# circuit.net
KiCad netlist of a schematic drawn in EAGLE
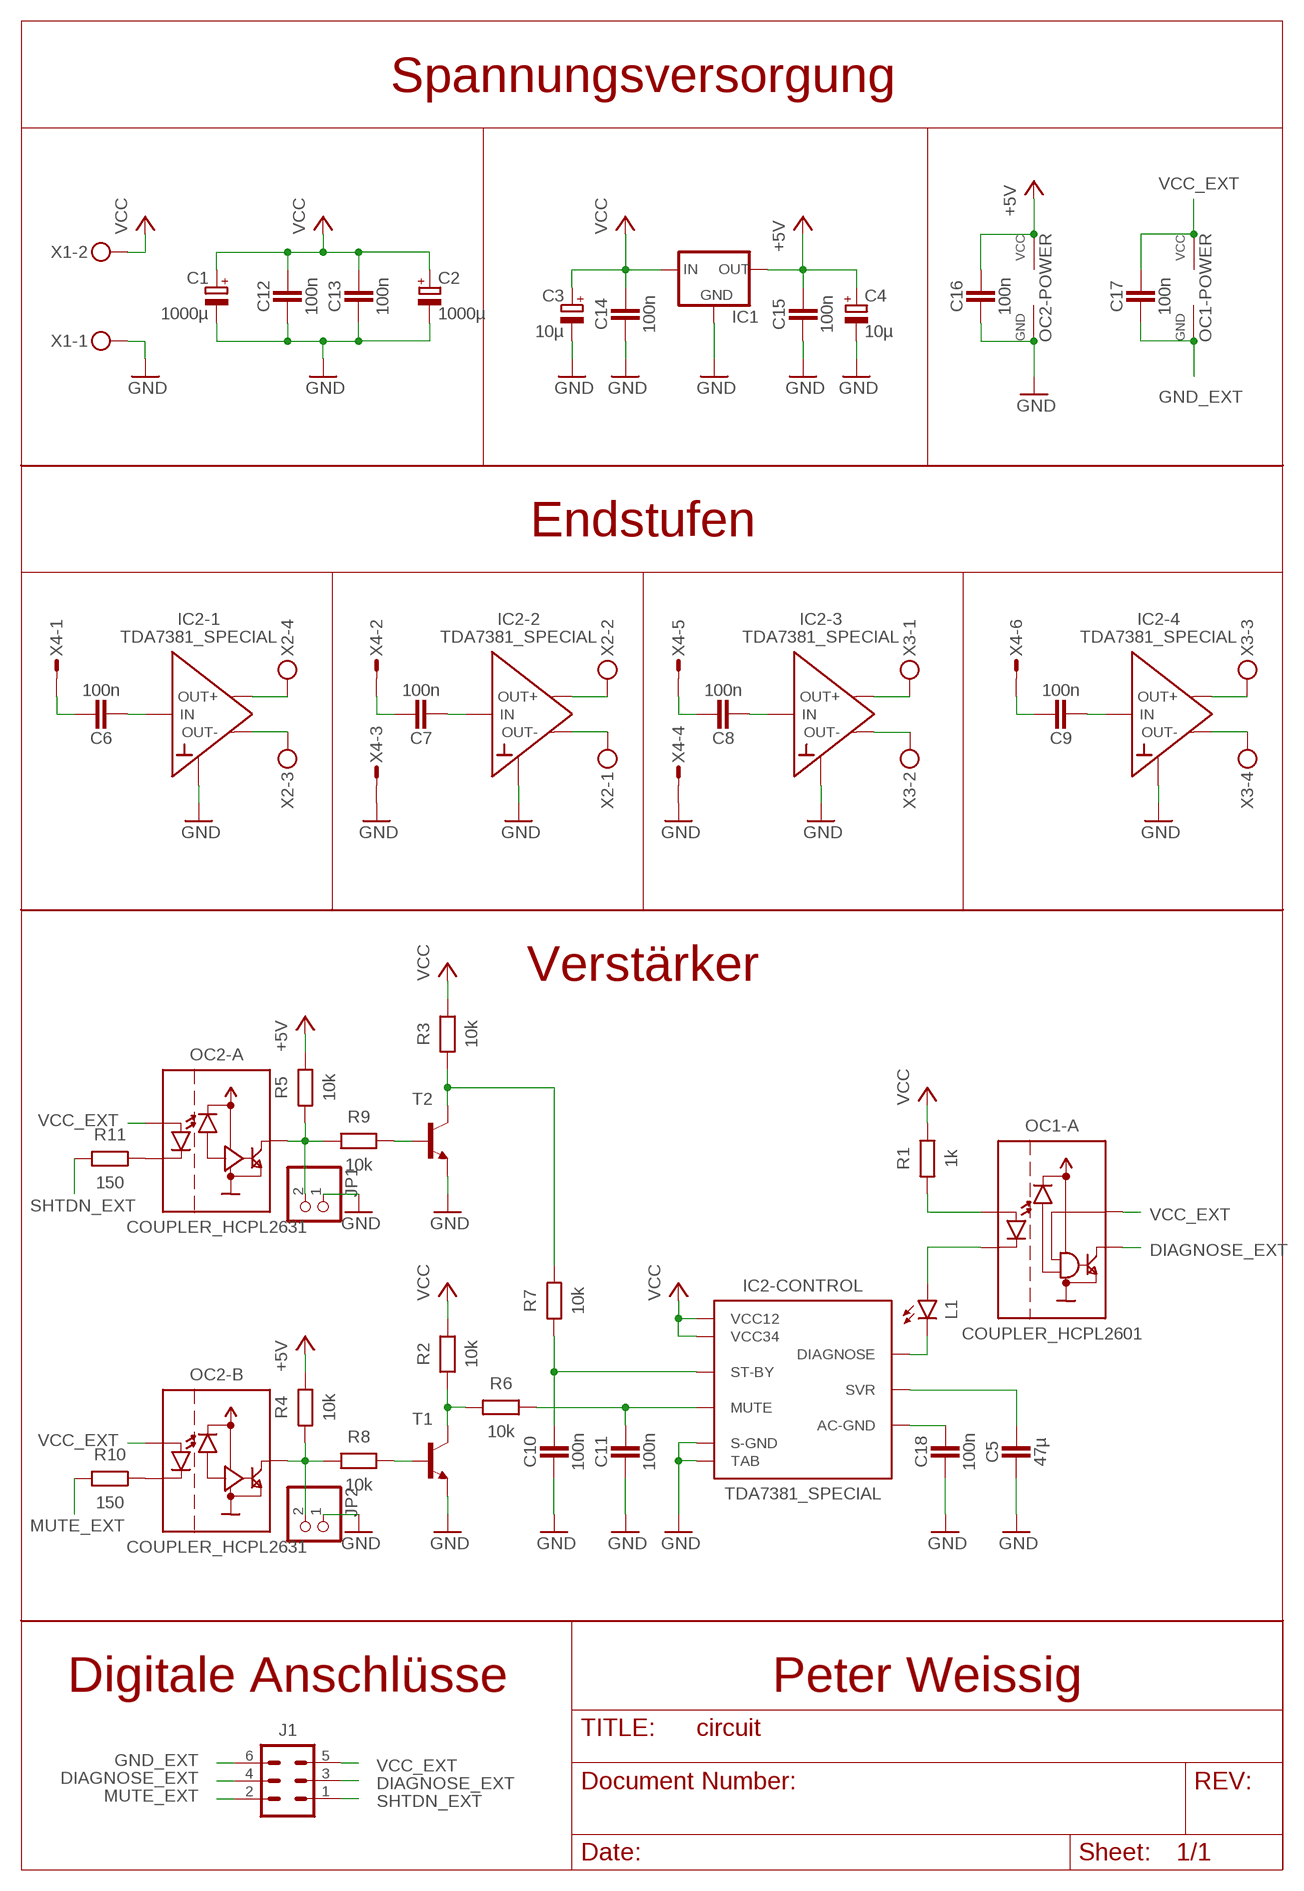
[diagram p0: schematic, sheet 1]

(export (version "E")
  (design (tool "Eeschema 10.0.6"))
  (components
    (comp (ref "C1")
      (value "1000µ")
      (footprint "eagle-import:E5-10,5")
      (libsource (lib "eagle-import") (part "CPOL-EUE5-10.5"))
    )
    (comp (ref "C2")
      (value "1000µ")
      (footprint "eagle-import:E5-10,5")
      (libsource (lib "eagle-import") (part "CPOL-EUE5-10.5"))
    )
    (comp (ref "C3")
      (value "10µ")
      (footprint "eagle-import:E2-5")
      (libsource (lib "eagle-import") (part "CPOL-EUE2-5"))
    )
    (comp (ref "C4")
      (value "10µ")
      (footprint "eagle-import:E2-5")
      (libsource (lib "eagle-import") (part "CPOL-EUE2-5"))
    )
    (comp (ref "C5")
      (value "47µ")
      (footprint "eagle-import:SMD_2312S")
      (libsource (lib "eagle-import") (part "CAPACITATOR-2312S"))
    )
    (comp (ref "C6")
      (value "100n")
      (footprint "eagle-import:C_THT_3")
      (libsource (lib "eagle-import") (part "CAPACITATOR-5MM"))
    )
    (comp (ref "C7")
      (value "100n")
      (footprint "eagle-import:C_THT_3")
      (libsource (lib "eagle-import") (part "CAPACITATOR-5MM"))
    )
    (comp (ref "C8")
      (value "100n")
      (footprint "eagle-import:C_THT_3")
      (libsource (lib "eagle-import") (part "CAPACITATOR-5MM"))
    )
    (comp (ref "C9")
      (value "100n")
      (footprint "eagle-import:C_THT_3")
      (libsource (lib "eagle-import") (part "CAPACITATOR-5MM"))
    )
    (comp (ref "C10")
      (value "100n")
      (footprint "eagle-import:C_THT_3")
      (libsource (lib "eagle-import") (part "CAPACITATOR-5MM"))
    )
    (comp (ref "C11")
      (value "100n")
      (footprint "eagle-import:C_THT_3")
      (libsource (lib "eagle-import") (part "CAPACITATOR-5MM"))
    )
    (comp (ref "C12")
      (value "100n")
      (footprint "eagle-import:SMD_1206")
      (libsource (lib "eagle-import") (part "CAPACITATOR-1206"))
    )
    (comp (ref "C13")
      (value "100n")
      (footprint "eagle-import:SMD_1206")
      (libsource (lib "eagle-import") (part "CAPACITATOR-1206"))
    )
    (comp (ref "C14")
      (value "100n")
      (footprint "eagle-import:SMD_1206")
      (libsource (lib "eagle-import") (part "CAPACITATOR-1206"))
    )
    (comp (ref "C15")
      (value "100n")
      (footprint "eagle-import:SMD_1206")
      (libsource (lib "eagle-import") (part "CAPACITATOR-1206"))
    )
    (comp (ref "C16")
      (value "100n")
      (footprint "eagle-import:SMD_1206")
      (libsource (lib "eagle-import") (part "CAPACITATOR-1206"))
    )
    (comp (ref "C17")
      (value "100n")
      (footprint "eagle-import:SMD_1206")
      (libsource (lib "eagle-import") (part "CAPACITATOR-1206"))
    )
    (comp (ref "C18")
      (value "100n")
      (footprint "eagle-import:SMD_1206")
      (libsource (lib "eagle-import") (part "CAPACITATOR-1206"))
    )
    (comp (ref "IC1")
      (value "78XXS")
      (footprint "eagle-import:78XXS")
      (libsource (lib "eagle-import") (part "78XXS"))
    )
    (comp (ref "IC2")
      (value "TDA7381_SPECIAL")
      (footprint "eagle-import:IC_FLEXIWATT25_SPECIAL")
      (libsource (lib "eagle-import") (part "TDA7381_SPECIAL"))
    )
    (comp (ref "J1")
      (value "STECKER_WANNE_6")
      (footprint "eagle-import:STECKER_WANNE_6")
      (libsource (lib "eagle-import") (part "STECKER_WANNE_6"))
    )
    (comp (ref "JP1")
      (value "PINHD-1X2")
      (footprint "eagle-import:1X02")
      (libsource (lib "eagle-import") (part "PINHD-1X2"))
    )
    (comp (ref "JP2")
      (value "PINHD-1X2")
      (footprint "eagle-import:1X02")
      (libsource (lib "eagle-import") (part "PINHD-1X2"))
    )
    (comp (ref "L1")
      (value "LED-3MM")
      (footprint "eagle-import:LED_3MM")
      (libsource (lib "eagle-import") (part "LED-3MM"))
    )
    (comp (ref "OC1")
      (value "COUPLER_HCPL2601")
      (footprint "eagle-import:IC_DIL08")
      (libsource (lib "eagle-import") (part "COUPLER_HCPL2601"))
    )
    (comp (ref "OC2")
      (value "COUPLER_HCPL2631")
      (footprint "eagle-import:IC_DIL08")
      (libsource (lib "eagle-import") (part "COUPLER_HCPL2631"))
    )
    (comp (ref "R1")
      (value "1k")
      (footprint "eagle-import:R_THT_4")
      (libsource (lib "eagle-import") (part "RESISTOR-10MM"))
    )
    (comp (ref "R2")
      (value "10k")
      (footprint "eagle-import:R_THT_4")
      (libsource (lib "eagle-import") (part "RESISTOR-10MM"))
    )
    (comp (ref "R3")
      (value "10k")
      (footprint "eagle-import:R_THT_4")
      (libsource (lib "eagle-import") (part "RESISTOR-10MM"))
    )
    (comp (ref "R4")
      (value "10k")
      (footprint "eagle-import:R_THT_4")
      (libsource (lib "eagle-import") (part "RESISTOR-10MM"))
    )
    (comp (ref "R5")
      (value "10k")
      (footprint "eagle-import:R_THT_4")
      (libsource (lib "eagle-import") (part "RESISTOR-10MM"))
    )
    (comp (ref "R6")
      (value "10k")
      (footprint "eagle-import:R_THT_4")
      (libsource (lib "eagle-import") (part "RESISTOR-10MM"))
    )
    (comp (ref "R7")
      (value "10k")
      (footprint "eagle-import:R_THT_4")
      (libsource (lib "eagle-import") (part "RESISTOR-10MM"))
    )
    (comp (ref "R8")
      (value "10k")
      (footprint "eagle-import:SMD_1206")
      (libsource (lib "eagle-import") (part "RESISTOR-1206"))
    )
    (comp (ref "R9")
      (value "10k")
      (footprint "eagle-import:SMD_1206")
      (libsource (lib "eagle-import") (part "RESISTOR-1206"))
    )
    (comp (ref "R10")
      (value "150")
      (footprint "eagle-import:SMD_1206")
      (libsource (lib "eagle-import") (part "RESISTOR-1206"))
    )
    (comp (ref "R11")
      (value "150")
      (footprint "eagle-import:SMD_1206")
      (libsource (lib "eagle-import") (part "RESISTOR-1206"))
    )
    (comp (ref "T1")
      (value "BC548-NPN-TO92-CBE")
      (footprint "eagle-import:TO92-CBE")
      (libsource (lib "eagle-import") (part "-NPN-TO92-CBEBC548"))
    )
    (comp (ref "T2")
      (value "BC548-NPN-TO92-CBE")
      (footprint "eagle-import:TO92-CBE")
      (libsource (lib "eagle-import") (part "-NPN-TO92-CBEBC548"))
    )
    (comp (ref "X1")
      (value "STECKER_SPG_2")
      (footprint "eagle-import:STECKER_SPG_2")
      (libsource (lib "eagle-import") (part "STECKER_SPG_2"))
    )
    (comp (ref "X2")
      (value "STECKER_SPG_4")
      (footprint "eagle-import:STECKER_SPG_4")
      (libsource (lib "eagle-import") (part "STECKER_SPG_4"))
    )
    (comp (ref "X3")
      (value "STECKER_SPG_4")
      (footprint "eagle-import:STECKER_SPG_4")
      (libsource (lib "eagle-import") (part "STECKER_SPG_4"))
    )
    (comp (ref "X4")
      (value "STECKER_MICROMATCH_6")
      (footprint "eagle-import:STECKER_MICROMATCH_6")
      (libsource (lib "eagle-import") (part "STECKER_MICROMATCH_6"))
    )
  )
  (nets
    (net (code "1") (name "+5V") (class "Default")
      (node (ref "C15") (pin "1") (pinfunction "1_1") (pintype "passive"))
      (node (ref "C16") (pin "1") (pinfunction "1_1") (pintype "passive"))
      (node (ref "C4") (pin "+") (pinfunction "+_+") (pintype "passive"))
      (node (ref "IC1") (pin "OUT") (pinfunction "OUT_OUT") (pintype "passive"))
      (node (ref "OC2") (pin "8") (pinfunction "VCC_8") (pintype "power_in"))
      (node (ref "R4") (pin "2") (pinfunction "P2_2") (pintype "passive"))
      (node (ref "R5") (pin "2") (pinfunction "P2_2") (pintype "passive"))
    )
    (net (code "2") (name "/DIAGNOSE_EXT") (class "Default")
      (node (ref "J1") (pin "3") (pinfunction "3_3") (pintype "passive"))
      (node (ref "J1") (pin "4") (pinfunction "4_4") (pintype "passive"))
      (node (ref "OC1") (pin "6") (pinfunction "O_6") (pintype "open_collector"))
    )
    (net (code "3") (name "/GND_EXT") (class "Default")
      (node (ref "C17") (pin "2") (pinfunction "2_2") (pintype "passive"))
      (node (ref "J1") (pin "6") (pinfunction "6_6") (pintype "passive"))
      (node (ref "OC1") (pin "5") (pinfunction "GND_5") (pintype "power_in"))
    )
    (net (code "4") (name "/MUTE_EXT") (class "Default")
      (node (ref "J1") (pin "2") (pinfunction "2_2") (pintype "passive"))
      (node (ref "R10") (pin "2") (pinfunction "P2_2") (pintype "passive"))
    )
    (net (code "5") (name "/SHTDN_EXT") (class "Default")
      (node (ref "J1") (pin "1") (pinfunction "1_1") (pintype "passive"))
      (node (ref "R11") (pin "2") (pinfunction "P2_2") (pintype "passive"))
    )
    (net (code "6") (name "/VCC_EXT") (class "Default")
      (node (ref "C17") (pin "1") (pinfunction "1_1") (pintype "passive"))
      (node (ref "J1") (pin "5") (pinfunction "5_5") (pintype "passive"))
      (node (ref "OC1") (pin "7") (pinfunction "I_EN_7") (pintype "input"))
      (node (ref "OC1") (pin "8") (pinfunction "VCC_8") (pintype "power_in"))
      (node (ref "OC2") (pin "1") (pinfunction "I_A_1") (pintype "input"))
      (node (ref "OC2") (pin "4") (pinfunction "I_A_4") (pintype "input"))
    )
    (net (code "7") (name "GND") (class "Default")
      (node (ref "C1") (pin "-") (pinfunction "-_-") (pintype "passive"))
      (node (ref "C10") (pin "1") (pinfunction "1_1") (pintype "passive"))
      (node (ref "C11") (pin "1") (pinfunction "1_1") (pintype "passive"))
      (node (ref "C12") (pin "2") (pinfunction "2_2") (pintype "passive"))
      (node (ref "C13") (pin "2") (pinfunction "2_2") (pintype "passive"))
      (node (ref "C14") (pin "2") (pinfunction "2_2") (pintype "passive"))
      (node (ref "C15") (pin "2") (pinfunction "2_2") (pintype "passive"))
      (node (ref "C16") (pin "2") (pinfunction "2_2") (pintype "passive"))
      (node (ref "C18") (pin "2") (pinfunction "2_2") (pintype "passive"))
      (node (ref "C2") (pin "-") (pinfunction "-_-") (pintype "passive"))
      (node (ref "C3") (pin "-") (pinfunction "-_-") (pintype "passive"))
      (node (ref "C4") (pin "-") (pinfunction "-_-") (pintype "passive"))
      (node (ref "C5") (pin "2") (pinfunction "2_2") (pintype "passive"))
      (node (ref "IC1") (pin "GND") (pinfunction "GND_GND") (pintype "input"))
      (node (ref "IC2") (pin "1") (pinfunction "TAB_1") (pintype "input"))
      (node (ref "IC2") (pin "13") (pinfunction "S-GND_13") (pintype "input"))
      (node (ref "IC2") (pin "18") (pinfunction "GND_18") (pintype "power_in"))
      (node (ref "IC2") (pin "2") (pinfunction "GND_2") (pintype "power_in"))
      (node (ref "IC2") (pin "24") (pinfunction "GND_24") (pintype "power_in"))
      (node (ref "IC2") (pin "8") (pinfunction "GND_8") (pintype "power_in"))
      (node (ref "JP1") (pin "1") (pinfunction "1_1") (pintype "passive"))
      (node (ref "JP2") (pin "1") (pinfunction "1_1") (pintype "passive"))
      (node (ref "OC2") (pin "5") (pinfunction "GND_5") (pintype "power_in"))
      (node (ref "T1") (pin "E") (pinfunction "E_E") (pintype "passive"))
      (node (ref "T2") (pin "E") (pinfunction "E_E") (pintype "passive"))
      (node (ref "X1") (pin "1") (pinfunction "KL_1") (pintype "passive"))
      (node (ref "X4") (pin "3") (pinfunction "S_3") (pintype "passive"))
      (node (ref "X4") (pin "4") (pinfunction "S_4") (pintype "passive"))
    )
    (net (code "8") (name "Net-(IC2A-IN)") (class "Default")
      (node (ref "C6") (pin "2") (pinfunction "2_2") (pintype "passive"))
      (node (ref "IC2") (pin "11") (pinfunction "IN_11") (pintype "input"))
    )
    (net (code "9") (name "Net-(IC2A-OUT+)") (class "Default")
      (node (ref "IC2") (pin "9") (pinfunction "OUT+_9") (pintype "output"))
      (node (ref "X2") (pin "4") (pinfunction "KL_4") (pintype "passive"))
    )
    (net (code "10") (name "Net-(IC2A-OUT-)") (class "Default")
      (node (ref "IC2") (pin "7") (pinfunction "OUT-_7") (pintype "output"))
      (node (ref "X2") (pin "3") (pinfunction "KL_3") (pintype "passive"))
    )
    (net (code "11") (name "Net-(IC2B-IN)") (class "Default")
      (node (ref "C7") (pin "2") (pinfunction "2_2") (pintype "passive"))
      (node (ref "IC2") (pin "12") (pinfunction "IN_12") (pintype "input"))
    )
    (net (code "12") (name "Net-(IC2B-OUT+)") (class "Default")
      (node (ref "IC2") (pin "5") (pinfunction "OUT+_5") (pintype "output"))
      (node (ref "X2") (pin "2") (pinfunction "KL_2") (pintype "passive"))
    )
    (net (code "13") (name "Net-(IC2B-OUT-)") (class "Default")
      (node (ref "IC2") (pin "3") (pinfunction "OUT-_3") (pintype "output"))
      (node (ref "X2") (pin "1") (pinfunction "KL_1") (pintype "passive"))
    )
    (net (code "14") (name "Net-(IC2C-IN)") (class "Default")
      (node (ref "C8") (pin "2") (pinfunction "2_2") (pintype "passive"))
      (node (ref "IC2") (pin "15") (pinfunction "IN_15") (pintype "input"))
    )
    (net (code "15") (name "Net-(IC2C-OUT+)") (class "Default")
      (node (ref "IC2") (pin "17") (pinfunction "OUT+_17") (pintype "output"))
      (node (ref "X3") (pin "1") (pinfunction "KL_1") (pintype "passive"))
    )
    (net (code "16") (name "Net-(IC2C-OUT-)") (class "Default")
      (node (ref "IC2") (pin "19") (pinfunction "OUT-_19") (pintype "output"))
      (node (ref "X3") (pin "2") (pinfunction "KL_2") (pintype "passive"))
    )
    (net (code "17") (name "Net-(IC2D-IN)") (class "Default")
      (node (ref "C9") (pin "2") (pinfunction "2_2") (pintype "passive"))
      (node (ref "IC2") (pin "14") (pinfunction "IN_14") (pintype "input"))
    )
    (net (code "18") (name "Net-(IC2D-OUT+)") (class "Default")
      (node (ref "IC2") (pin "21") (pinfunction "OUT+_21") (pintype "output"))
      (node (ref "X3") (pin "3") (pinfunction "KL_3") (pintype "passive"))
    )
    (net (code "19") (name "Net-(IC2D-OUT-)") (class "Default")
      (node (ref "IC2") (pin "23") (pinfunction "OUT-_23") (pintype "output"))
      (node (ref "X3") (pin "4") (pinfunction "KL_4") (pintype "passive"))
    )
    (net (code "20") (name "Net-(IC2E-AC-GND)") (class "Default")
      (node (ref "C18") (pin "1") (pinfunction "1_1") (pintype "passive"))
      (node (ref "IC2") (pin "16") (pinfunction "AC-GND_16") (pintype "power_in"))
    )
    (net (code "21") (name "Net-(IC2E-DIAGNOSE)") (class "Default")
      (node (ref "IC2") (pin "25") (pinfunction "DIAGNOSE_25") (pintype "open_collector"))
      (node (ref "L1") (pin "K") (pinfunction "C_K") (pintype "passive"))
    )
    (net (code "22") (name "Net-(IC2E-MUTE)") (class "Default")
      (node (ref "C11") (pin "2") (pinfunction "2_2") (pintype "passive"))
      (node (ref "IC2") (pin "22") (pinfunction "MUTE_22") (pintype "input"))
      (node (ref "R6") (pin "1") (pinfunction "P1_1") (pintype "passive"))
    )
    (net (code "23") (name "Net-(IC2E-ST-BY)") (class "Default")
      (node (ref "C10") (pin "2") (pinfunction "2_2") (pintype "passive"))
      (node (ref "IC2") (pin "4") (pinfunction "ST-BY_4") (pintype "input"))
      (node (ref "R7") (pin "1") (pinfunction "P1_1") (pintype "passive"))
    )
    (net (code "24") (name "Net-(IC2E-SVR)") (class "Default")
      (node (ref "C5") (pin "1") (pinfunction "1_1") (pintype "passive"))
      (node (ref "IC2") (pin "10") (pinfunction "SVR_10") (pintype "power_in"))
    )
    (net (code "25") (name "Net-(OC1A-I_A)") (class "Default")
      (node (ref "OC1") (pin "2") (pinfunction "I_A_2") (pintype "input"))
      (node (ref "R1") (pin "1") (pinfunction "P1_1") (pintype "passive"))
    )
    (net (code "26") (name "Net-(OC1A-I_K)") (class "Default")
      (node (ref "L1") (pin "A") (pinfunction "A_A") (pintype "passive"))
      (node (ref "OC1") (pin "3") (pinfunction "I_K_3") (pintype "input"))
    )
    (net (code "27") (name "Net-(OC2A-I_K)") (class "Default")
      (node (ref "OC2") (pin "2") (pinfunction "I_K_2") (pintype "input"))
      (node (ref "R11") (pin "1") (pinfunction "P1_1") (pintype "passive"))
    )
    (net (code "28") (name "Net-(OC2A-O)") (class "Default")
      (node (ref "JP1") (pin "2") (pinfunction "2_2") (pintype "passive"))
      (node (ref "OC2") (pin "7") (pinfunction "O_7") (pintype "open_collector"))
      (node (ref "R5") (pin "1") (pinfunction "P1_1") (pintype "passive"))
      (node (ref "R9") (pin "1") (pinfunction "P1_1") (pintype "passive"))
    )
    (net (code "29") (name "Net-(OC2B-I_K)") (class "Default")
      (node (ref "OC2") (pin "3") (pinfunction "I_K_3") (pintype "input"))
      (node (ref "R10") (pin "1") (pinfunction "P1_1") (pintype "passive"))
    )
    (net (code "30") (name "Net-(OC2B-O)") (class "Default")
      (node (ref "JP2") (pin "2") (pinfunction "2_2") (pintype "passive"))
      (node (ref "OC2") (pin "6") (pinfunction "O_6") (pintype "open_collector"))
      (node (ref "R4") (pin "1") (pinfunction "P1_1") (pintype "passive"))
      (node (ref "R8") (pin "1") (pinfunction "P1_1") (pintype "passive"))
    )
    (net (code "31") (name "Net-(R2-P2)") (class "Default")
      (node (ref "R2") (pin "2") (pinfunction "P2_2") (pintype "passive"))
      (node (ref "R6") (pin "2") (pinfunction "P2_2") (pintype "passive"))
      (node (ref "T1") (pin "C") (pinfunction "C_C") (pintype "passive"))
    )
    (net (code "32") (name "Net-(R3-P2)") (class "Default")
      (node (ref "R3") (pin "2") (pinfunction "P2_2") (pintype "passive"))
      (node (ref "R7") (pin "2") (pinfunction "P2_2") (pintype "passive"))
      (node (ref "T2") (pin "C") (pinfunction "C_C") (pintype "passive"))
    )
    (net (code "33") (name "Net-(R8-P2)") (class "Default")
      (node (ref "R8") (pin "2") (pinfunction "P2_2") (pintype "passive"))
      (node (ref "T1") (pin "B") (pinfunction "B_B") (pintype "passive"))
    )
    (net (code "34") (name "Net-(R9-P2)") (class "Default")
      (node (ref "R9") (pin "2") (pinfunction "P2_2") (pintype "passive"))
      (node (ref "T2") (pin "B") (pinfunction "B_B") (pintype "passive"))
    )
    (net (code "35") (name "Net-(X4A-S)") (class "Default")
      (node (ref "C6") (pin "1") (pinfunction "1_1") (pintype "passive"))
      (node (ref "X4") (pin "1") (pinfunction "S_1") (pintype "passive"))
    )
    (net (code "36") (name "Net-(X4B-S)") (class "Default")
      (node (ref "C7") (pin "1") (pinfunction "1_1") (pintype "passive"))
      (node (ref "X4") (pin "2") (pinfunction "S_2") (pintype "passive"))
    )
    (net (code "37") (name "Net-(X4E-S)") (class "Default")
      (node (ref "C8") (pin "1") (pinfunction "1_1") (pintype "passive"))
      (node (ref "X4") (pin "5") (pinfunction "S_5") (pintype "passive"))
    )
    (net (code "38") (name "Net-(X4F-S)") (class "Default")
      (node (ref "C9") (pin "1") (pinfunction "1_1") (pintype "passive"))
      (node (ref "X4") (pin "6") (pinfunction "S_6") (pintype "passive"))
    )
    (net (code "39") (name "VCC") (class "Default")
      (node (ref "C1") (pin "+") (pinfunction "+_+") (pintype "passive"))
      (node (ref "C12") (pin "1") (pinfunction "1_1") (pintype "passive"))
      (node (ref "C13") (pin "1") (pinfunction "1_1") (pintype "passive"))
      (node (ref "C14") (pin "1") (pinfunction "1_1") (pintype "passive"))
      (node (ref "C2") (pin "+") (pinfunction "+_+") (pintype "passive"))
      (node (ref "C3") (pin "+") (pinfunction "+_+") (pintype "passive"))
      (node (ref "IC1") (pin "IN") (pinfunction "IN_IN") (pintype "input"))
      (node (ref "IC2") (pin "20") (pinfunction "VCC34_20") (pintype "input"))
      (node (ref "IC2") (pin "6") (pinfunction "VCC12_6") (pintype "input"))
      (node (ref "R1") (pin "2") (pinfunction "P2_2") (pintype "passive"))
      (node (ref "R2") (pin "1") (pinfunction "P1_1") (pintype "passive"))
      (node (ref "R3") (pin "1") (pinfunction "P1_1") (pintype "passive"))
      (node (ref "X1") (pin "2") (pinfunction "KL_2") (pintype "passive"))
    )
  )
)
